# TapTempoMk2.net
KiCad netlist of a schematic drawn in EAGLE
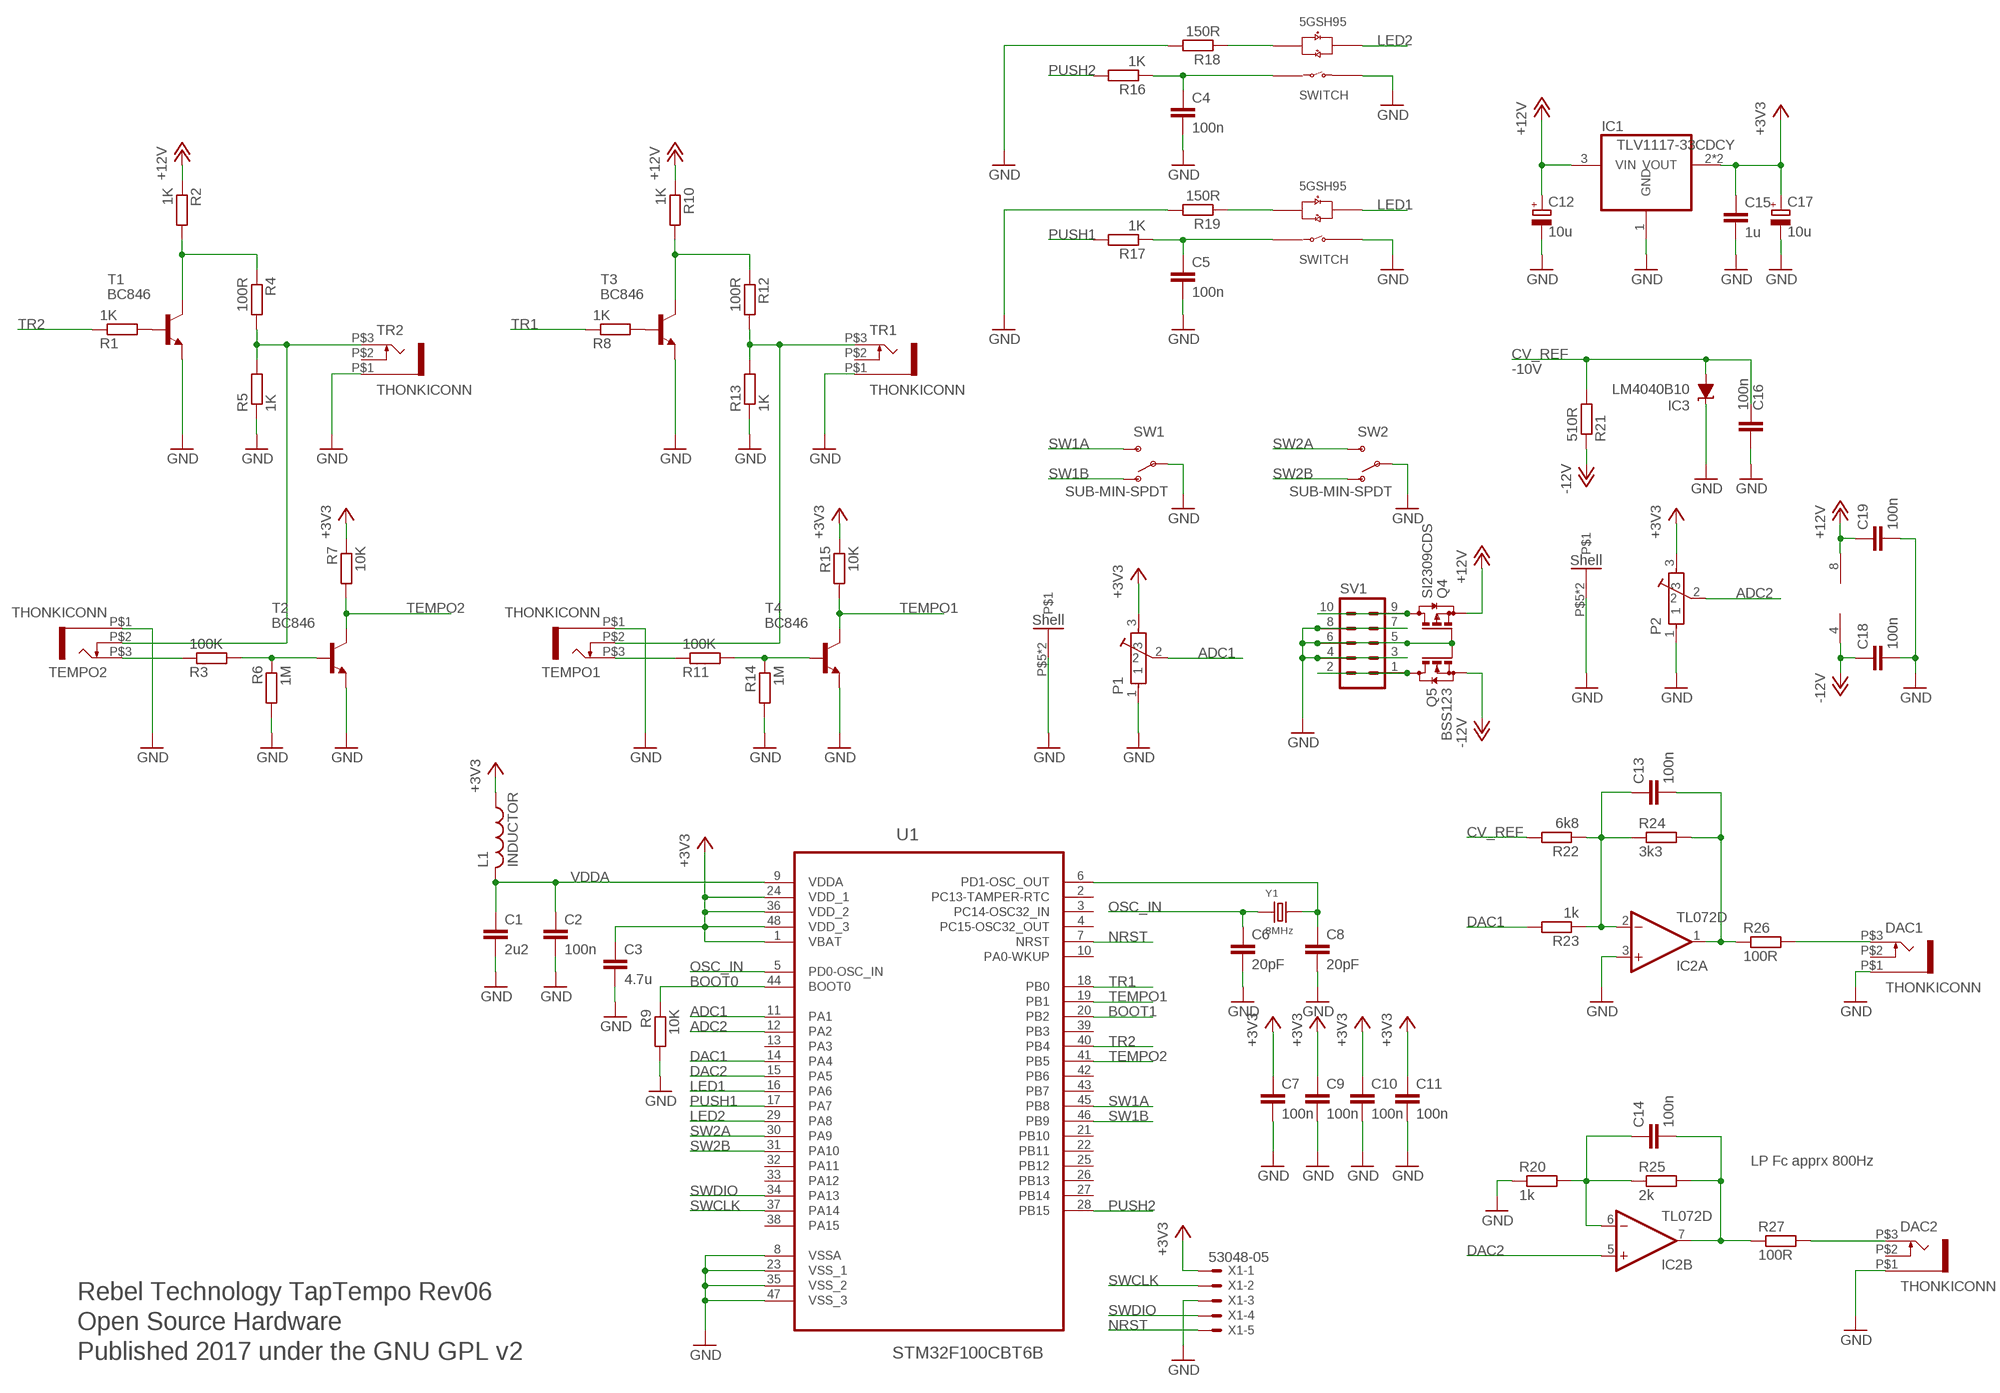
[diagram p0: schematic, sheet 1]

(export (version "E")
  (design (tool "Eeschema 10.0.6"))
  (components
    (comp (ref "C1")
      (value "2u2")
      (footprint "eagle-import:C0603")
      (libsource (lib "eagle-import") (part "C-EUC0603"))
    )
    (comp (ref "C2")
      (value "100n")
      (footprint "eagle-import:C0603")
      (libsource (lib "eagle-import") (part "C-EUC0603"))
    )
    (comp (ref "C3")
      (value "4.7u")
      (footprint "eagle-import:C0603")
      (libsource (lib "eagle-import") (part "C-EUC0603"))
    )
    (comp (ref "C4")
      (value "100n")
      (footprint "eagle-import:C0603")
      (libsource (lib "eagle-import") (part "C-EUC0603"))
    )
    (comp (ref "C5")
      (value "100n")
      (footprint "eagle-import:C0603")
      (libsource (lib "eagle-import") (part "C-EUC0603"))
    )
    (comp (ref "C6")
      (value "20pF")
      (footprint "eagle-import:C0603")
      (libsource (lib "eagle-import") (part "C-EUC0603"))
    )
    (comp (ref "C7")
      (value "100n")
      (footprint "eagle-import:C0603")
      (libsource (lib "eagle-import") (part "C-EUC0603"))
    )
    (comp (ref "C8")
      (value "20pF")
      (footprint "eagle-import:C0603")
      (libsource (lib "eagle-import") (part "C-EUC0603"))
    )
    (comp (ref "C9")
      (value "100n")
      (footprint "eagle-import:C0603")
      (libsource (lib "eagle-import") (part "C-EUC0603"))
    )
    (comp (ref "C10")
      (value "100n")
      (footprint "eagle-import:C0603")
      (libsource (lib "eagle-import") (part "C-EUC0603"))
    )
    (comp (ref "C11")
      (value "100n")
      (footprint "eagle-import:C0603")
      (libsource (lib "eagle-import") (part "C-EUC0603"))
    )
    (comp (ref "C12")
      (value "10u")
      (footprint "eagle-import:153CLV-0405")
      (libsource (lib "eagle-import") (part "CPOL-EU153CLV-0405"))
    )
    (comp (ref "C13")
      (value "100n")
      (footprint "eagle-import:C0603")
      (libsource (lib "eagle-import") (part "C-EUC0603"))
    )
    (comp (ref "C14")
      (value "100n")
      (footprint "eagle-import:C0603")
      (libsource (lib "eagle-import") (part "C-EUC0603"))
    )
    (comp (ref "C15")
      (value "1u")
      (footprint "eagle-import:C0603")
      (libsource (lib "eagle-import") (part "C-EUC0603"))
    )
    (comp (ref "C16")
      (value "100n")
      (footprint "eagle-import:C0603")
      (libsource (lib "eagle-import") (part "C-EUC0603"))
    )
    (comp (ref "C17")
      (value "10u")
      (footprint "eagle-import:153CLV-0405")
      (libsource (lib "eagle-import") (part "CPOL-EU153CLV-0405"))
    )
    (comp (ref "C18")
      (value "100n")
      (footprint "eagle-import:C0603")
      (libsource (lib "eagle-import") (part "C-EUC0603"))
    )
    (comp (ref "C19")
      (value "100n")
      (footprint "eagle-import:C0603")
      (libsource (lib "eagle-import") (part "C-EUC0603"))
    )
    (comp (ref "DAC1")
      (value "THONKICONN")
      (footprint "eagle-import:THONKICONN")
      (libsource (lib "eagle-import") (part "THONKICONN"))
    )
    (comp (ref "DAC2")
      (value "THONKICONN")
      (footprint "eagle-import:THONKICONN")
      (libsource (lib "eagle-import") (part "THONKICONN"))
    )
    (comp (ref "IC1")
      (value "TLV1117-33CDCY")
      (footprint "eagle-import:SOT223")
      (fields (field (name "MPN") "REG1117"))
      (libsource (lib "eagle-import") (part "REG1117"))
    )
    (comp (ref "IC2")
      (value "TL072D")
      (footprint "eagle-import:SO08")
      (libsource (lib "eagle-import") (part "TL072D"))
    )
    (comp (ref "IC3")
      (value "LM4040B10")
      (footprint "eagle-import:DBZ_R-PDSO-G3")
      (fields (field (name "MF") "TEXAS INSTRUMENT CONNECTORS") (field (name "MPN") "LM4041C12QDBZT"))
      (libsource (lib "eagle-import") (part "LM4041DBZC12"))
    )
    (comp (ref "L1")
      (value "INDUCTOR")
      (footprint "eagle-import:0603")
      (libsource (lib "eagle-import") (part "INDUCTOR"))
    )
    (comp (ref "P1")
      (value "POT-ALPS-RK09L1140")
      (footprint "eagle-import:POT-ALPS-RK09L1140")
      (libsource (lib "eagle-import") (part "POT-ALPS-RK09L1140"))
    )
    (comp (ref "P2")
      (value "POT-ALPS-RK09L1140")
      (footprint "eagle-import:POT-ALPS-RK09L1140")
      (libsource (lib "eagle-import") (part "POT-ALPS-RK09L1140"))
    )
    (comp (ref "PUSH1")
      (value "5GTH9")
      (footprint "eagle-import:5GTH9")
      (libsource (lib "eagle-import") (part "5GTH9"))
    )
    (comp (ref "PUSH2")
      (value "5GTH9")
      (footprint "eagle-import:5GTH9")
      (libsource (lib "eagle-import") (part "5GTH9"))
    )
    (comp (ref "Q4")
      (value "SI2309CDS")
      (footprint "eagle-import:SOT23")
      (libsource (lib "eagle-import") (part "BSS84"))
    )
    (comp (ref "Q5")
      (value "BSS123")
      (footprint "eagle-import:SOT23")
      (libsource (lib "eagle-import") (part "BSS123"))
    )
    (comp (ref "R1")
      (value "1K")
      (footprint "eagle-import:0603")
      (libsource (lib "eagle-import") (part "R-EU_0603"))
    )
    (comp (ref "R2")
      (value "1K")
      (footprint "eagle-import:0603")
      (libsource (lib "eagle-import") (part "R-EU_0603"))
    )
    (comp (ref "R3")
      (value "100K")
      (footprint "eagle-import:0603")
      (libsource (lib "eagle-import") (part "R-EU_0603"))
    )
    (comp (ref "R4")
      (value "100R")
      (footprint "eagle-import:0603")
      (libsource (lib "eagle-import") (part "R-EU_0603"))
    )
    (comp (ref "R5")
      (value "1K")
      (footprint "eagle-import:0603")
      (libsource (lib "eagle-import") (part "R-EU_0603"))
    )
    (comp (ref "R6")
      (value "1M")
      (footprint "eagle-import:0603")
      (libsource (lib "eagle-import") (part "R-EU_0603"))
    )
    (comp (ref "R7")
      (value "10K")
      (footprint "eagle-import:0603")
      (libsource (lib "eagle-import") (part "R-EU_0603"))
    )
    (comp (ref "R8")
      (value "1K")
      (footprint "eagle-import:0603")
      (libsource (lib "eagle-import") (part "R-EU_0603"))
    )
    (comp (ref "R9")
      (value "10K")
      (footprint "eagle-import:0603")
      (libsource (lib "eagle-import") (part "R-EU_0603"))
    )
    (comp (ref "R10")
      (value "1K")
      (footprint "eagle-import:0603")
      (libsource (lib "eagle-import") (part "R-EU_0603"))
    )
    (comp (ref "R11")
      (value "100K")
      (footprint "eagle-import:0603")
      (libsource (lib "eagle-import") (part "R-EU_0603"))
    )
    (comp (ref "R12")
      (value "100R")
      (footprint "eagle-import:0603")
      (libsource (lib "eagle-import") (part "R-EU_0603"))
    )
    (comp (ref "R13")
      (value "1K")
      (footprint "eagle-import:0603")
      (libsource (lib "eagle-import") (part "R-EU_0603"))
    )
    (comp (ref "R14")
      (value "1M")
      (footprint "eagle-import:0603")
      (libsource (lib "eagle-import") (part "R-EU_0603"))
    )
    (comp (ref "R15")
      (value "10K")
      (footprint "eagle-import:0603")
      (libsource (lib "eagle-import") (part "R-EU_0603"))
    )
    (comp (ref "R16")
      (value "1K")
      (footprint "eagle-import:0603")
      (libsource (lib "eagle-import") (part "R-EU_0603"))
    )
    (comp (ref "R17")
      (value "1K")
      (footprint "eagle-import:0603")
      (libsource (lib "eagle-import") (part "R-EU_0603"))
    )
    (comp (ref "R18")
      (value "150R")
      (footprint "eagle-import:0603")
      (libsource (lib "eagle-import") (part "R-EU_0603"))
    )
    (comp (ref "R19")
      (value "150R")
      (footprint "eagle-import:0603")
      (libsource (lib "eagle-import") (part "R-EU_0603"))
    )
    (comp (ref "R20")
      (value "1k")
      (footprint "eagle-import:0603")
      (libsource (lib "eagle-import") (part "R-EU_0603"))
    )
    (comp (ref "R21")
      (value "510R")
      (footprint "eagle-import:0603")
      (libsource (lib "eagle-import") (part "R-EU_0603"))
    )
    (comp (ref "R22")
      (value "6k8")
      (footprint "eagle-import:0603")
      (libsource (lib "eagle-import") (part "R-EU_0603"))
    )
    (comp (ref "R23")
      (value "1k")
      (footprint "eagle-import:0603")
      (libsource (lib "eagle-import") (part "R-EU_0603"))
    )
    (comp (ref "R24")
      (value "3k3")
      (footprint "eagle-import:0603")
      (libsource (lib "eagle-import") (part "R-EU_0603"))
    )
    (comp (ref "R25")
      (value "2k")
      (footprint "eagle-import:0603")
      (libsource (lib "eagle-import") (part "R-EU_0603"))
    )
    (comp (ref "R26")
      (value "100R")
      (footprint "eagle-import:0603")
      (libsource (lib "eagle-import") (part "R-EU_0603"))
    )
    (comp (ref "R27")
      (value "100R")
      (footprint "eagle-import:0603")
      (libsource (lib "eagle-import") (part "R-EU_0603"))
    )
    (comp (ref "SV1")
      (value "MA05-2")
      (footprint "eagle-import:MA05-2")
      (libsource (lib "eagle-import") (part "MA05-2"))
    )
    (comp (ref "SW1")
      (value "SUB-MIN-SPDT")
      (footprint "eagle-import:SUB-MIN-SPDT")
      (libsource (lib "eagle-import") (part "SUB-MIN-SPDT"))
    )
    (comp (ref "SW2")
      (value "SUB-MIN-SPDT")
      (footprint "eagle-import:SUB-MIN-SPDT")
      (libsource (lib "eagle-import") (part "SUB-MIN-SPDT"))
    )
    (comp (ref "T1")
      (value "BC846")
      (footprint "eagle-import:SOT23")
      (libsource (lib "eagle-import") (part "BC846"))
    )
    (comp (ref "T2")
      (value "BC846")
      (footprint "eagle-import:SOT23")
      (libsource (lib "eagle-import") (part "BC846"))
    )
    (comp (ref "T3")
      (value "BC846")
      (footprint "eagle-import:SOT23")
      (libsource (lib "eagle-import") (part "BC846"))
    )
    (comp (ref "T4")
      (value "BC846")
      (footprint "eagle-import:SOT23")
      (libsource (lib "eagle-import") (part "BC846"))
    )
    (comp (ref "TEMPO1")
      (value "THONKICONN")
      (footprint "eagle-import:THONKICONN")
      (libsource (lib "eagle-import") (part "THONKICONN"))
    )
    (comp (ref "TEMPO2")
      (value "THONKICONN")
      (footprint "eagle-import:THONKICONN")
      (libsource (lib "eagle-import") (part "THONKICONN"))
    )
    (comp (ref "TR1")
      (value "THONKICONN")
      (footprint "eagle-import:THONKICONN")
      (libsource (lib "eagle-import") (part "THONKICONN"))
    )
    (comp (ref "TR2")
      (value "THONKICONN")
      (footprint "eagle-import:THONKICONN")
      (libsource (lib "eagle-import") (part "THONKICONN"))
    )
    (comp (ref "U1")
      (value "STM32F100CBT6B")
      (footprint "eagle-import:QFP50P900X900X160-48N")
      (libsource (lib "eagle-import") (part "STM32F100CBT6B"))
    )
    (comp (ref "X1")
      (value "53048-05")
      (footprint "eagle-import:53048-05")
      (fields (field (name "MF") "MOLEX") (field (name "MPN") "53048-0510"))
      (libsource (lib "eagle-import") (part "53?-05048"))
    )
    (comp (ref "Y1")
      (value "8MHz")
      (footprint "eagle-import:X2-SMD-5.0X3.2X1.3MM")
      (fields (field (name "MPN") "5032/2P"))
      (libsource (lib "eagle-import") (part "SMD-CRYSTAL-8MHZ-20PF-20PPM(2P-5.0X3.2MM)"))
    )
  )
  (nets
    (net (code "1") (name "+3V3") (class "Default")
      (node (ref "C10") (pin "1") (pinfunction "1_1") (pintype "passive"))
      (node (ref "C11") (pin "1") (pinfunction "1_1") (pintype "passive"))
      (node (ref "C15") (pin "1") (pinfunction "1_1") (pintype "passive"))
      (node (ref "C17") (pin "+") (pinfunction "+_+") (pintype "passive"))
      (node (ref "C3") (pin "1") (pinfunction "1_1") (pintype "passive"))
      (node (ref "C7") (pin "1") (pinfunction "1_1") (pintype "passive"))
      (node (ref "C9") (pin "1") (pinfunction "1_1") (pintype "passive"))
      (node (ref "IC1") (pin "2") (pinfunction "VOUT_2") (pintype "output"))
      (node (ref "IC1") (pin "4") (pinfunction "VOUT_4") (pintype "output"))
      (node (ref "L1") (pin "1") (pinfunction "1_1") (pintype "passive"))
      (node (ref "P1") (pin "3") (pinfunction "3_3") (pintype "bidirectional"))
      (node (ref "P2") (pin "3") (pinfunction "3_3") (pintype "bidirectional"))
      (node (ref "R15") (pin "1") (pinfunction "1_1") (pintype "passive"))
      (node (ref "R7") (pin "1") (pinfunction "1_1") (pintype "passive"))
      (node (ref "U1") (pin "1") (pinfunction "VBAT_1") (pintype "power_in"))
      (node (ref "U1") (pin "24") (pinfunction "VDD_1_24") (pintype "power_in"))
      (node (ref "U1") (pin "36") (pinfunction "VDD_2_36") (pintype "power_in"))
      (node (ref "U1") (pin "48") (pinfunction "VDD_3_48") (pintype "power_in"))
      (node (ref "X1") (pin "1") (pinfunction "S_1") (pintype "passive"))
    )
    (net (code "2") (name "+12V") (class "Default")
      (node (ref "C12") (pin "+") (pinfunction "+_+") (pintype "passive"))
      (node (ref "C19") (pin "1") (pinfunction "1_1") (pintype "passive"))
      (node (ref "IC1") (pin "3") (pinfunction "VIN_3") (pintype "input"))
      (node (ref "IC2") (pin "8") (pinfunction "V+_8") (pintype "power_in"))
      (node (ref "Q4") (pin "2") (pinfunction "S_2") (pintype "passive"))
      (node (ref "R10") (pin "1") (pinfunction "1_1") (pintype "passive"))
      (node (ref "R2") (pin "1") (pinfunction "1_1") (pintype "passive"))
    )
    (net (code "3") (name "-12V") (class "Default")
      (node (ref "C18") (pin "1") (pinfunction "1_1") (pintype "passive"))
      (node (ref "IC2") (pin "4") (pinfunction "V-_4") (pintype "power_in"))
      (node (ref "Q5") (pin "2") (pinfunction "S_2") (pintype "passive"))
      (node (ref "R21") (pin "1") (pinfunction "1_1") (pintype "passive"))
    )
    (net (code "4") (name "/ADC1") (class "Default")
      (node (ref "P1") (pin "2") (pinfunction "2_2") (pintype "bidirectional"))
      (node (ref "U1") (pin "11") (pinfunction "PA1_11") (pintype "bidirectional"))
    )
    (net (code "5") (name "/ADC2") (class "Default")
      (node (ref "P2") (pin "2") (pinfunction "2_2") (pintype "bidirectional"))
      (node (ref "U1") (pin "12") (pinfunction "PA2_12") (pintype "bidirectional"))
    )
    (net (code "6") (name "/BOOT0") (class "Default")
      (node (ref "R9") (pin "1") (pinfunction "1_1") (pintype "passive"))
      (node (ref "U1") (pin "44") (pinfunction "BOOT0_44") (pintype "input"))
    )
    (net (code "7") (name "/BOOT1") (class "Default")
      (node (ref "U1") (pin "20") (pinfunction "PB2_20") (pintype "bidirectional"))
    )
    (net (code "8") (name "/CV_REF") (class "Default")
      (node (ref "C16") (pin "1") (pinfunction "1_1") (pintype "passive"))
      (node (ref "IC3") (pin "2") (pinfunction "A_2") (pintype "passive"))
      (node (ref "R21") (pin "2") (pinfunction "2_2") (pintype "passive"))
      (node (ref "R22") (pin "2") (pinfunction "2_2") (pintype "passive"))
    )
    (net (code "9") (name "/DAC1") (class "Default")
      (node (ref "R23") (pin "2") (pinfunction "2_2") (pintype "passive"))
      (node (ref "U1") (pin "14") (pinfunction "PA4_14") (pintype "bidirectional"))
    )
    (net (code "10") (name "/DAC2") (class "Default")
      (node (ref "IC2") (pin "5") (pinfunction "+IN_5") (pintype "input"))
      (node (ref "U1") (pin "15") (pinfunction "PA5_15") (pintype "bidirectional"))
    )
    (net (code "11") (name "/LED1") (class "Default")
      (node (ref "PUSH1") (pin "+3") (pinfunction "LED_R+_+3") (pintype "bidirectional"))
      (node (ref "U1") (pin "16") (pinfunction "PA6_16") (pintype "bidirectional"))
    )
    (net (code "12") (name "/LED2") (class "Default")
      (node (ref "PUSH2") (pin "+3") (pinfunction "LED_R+_+3") (pintype "bidirectional"))
      (node (ref "U1") (pin "29") (pinfunction "PA8_29") (pintype "bidirectional"))
    )
    (net (code "13") (name "/NRST") (class "Default")
      (node (ref "U1") (pin "7") (pinfunction "NRST_7") (pintype "bidirectional"))
      (node (ref "X1") (pin "5") (pinfunction "S_5") (pintype "passive"))
    )
    (net (code "14") (name "/OSC_IN") (class "Default")
      (node (ref "C6") (pin "1") (pinfunction "1_1") (pintype "passive"))
      (node (ref "U1") (pin "5") (pinfunction "PD0-OSC_IN_5") (pintype "input"))
      (node (ref "Y1") (pin "1") (pinfunction "1_1") (pintype "passive"))
    )
    (net (code "15") (name "/PUSH1") (class "Default")
      (node (ref "R17") (pin "2") (pinfunction "2_2") (pintype "passive"))
      (node (ref "U1") (pin "17") (pinfunction "PA7_17") (pintype "bidirectional"))
    )
    (net (code "16") (name "/PUSH2") (class "Default")
      (node (ref "R16") (pin "2") (pinfunction "2_2") (pintype "passive"))
      (node (ref "U1") (pin "28") (pinfunction "PB15_28") (pintype "bidirectional"))
    )
    (net (code "17") (name "/SW1A") (class "Default")
      (node (ref "SW1") (pin "3") (pinfunction "S_3") (pintype "passive"))
      (node (ref "U1") (pin "45") (pinfunction "PB8_45") (pintype "bidirectional"))
    )
    (net (code "18") (name "/SW1B") (class "Default")
      (node (ref "SW1") (pin "1") (pinfunction "O_1") (pintype "passive"))
      (node (ref "U1") (pin "46") (pinfunction "PB9_46") (pintype "bidirectional"))
    )
    (net (code "19") (name "/SW2A") (class "Default")
      (node (ref "SW2") (pin "3") (pinfunction "S_3") (pintype "passive"))
      (node (ref "U1") (pin "30") (pinfunction "PA9_30") (pintype "bidirectional"))
    )
    (net (code "20") (name "/SW2B") (class "Default")
      (node (ref "SW2") (pin "1") (pinfunction "O_1") (pintype "passive"))
      (node (ref "U1") (pin "31") (pinfunction "PA10_31") (pintype "bidirectional"))
    )
    (net (code "21") (name "/SWCLK") (class "Default")
      (node (ref "U1") (pin "37") (pinfunction "PA14_37") (pintype "bidirectional"))
      (node (ref "X1") (pin "2") (pinfunction "S_2") (pintype "passive"))
    )
    (net (code "22") (name "/SWDIO") (class "Default")
      (node (ref "U1") (pin "34") (pinfunction "PA13_34") (pintype "bidirectional"))
      (node (ref "X1") (pin "4") (pinfunction "S_4") (pintype "passive"))
    )
    (net (code "23") (name "/TEMPO1") (class "Default")
      (node (ref "R15") (pin "2") (pinfunction "2_2") (pintype "passive"))
      (node (ref "T4") (pin "3") (pinfunction "C_3") (pintype "passive"))
      (node (ref "U1") (pin "19") (pinfunction "PB1_19") (pintype "bidirectional"))
    )
    (net (code "24") (name "/TEMPO2") (class "Default")
      (node (ref "R7") (pin "2") (pinfunction "2_2") (pintype "passive"))
      (node (ref "T2") (pin "3") (pinfunction "C_3") (pintype "passive"))
      (node (ref "U1") (pin "41") (pinfunction "PB5_41") (pintype "bidirectional"))
    )
    (net (code "25") (name "/TR1") (class "Default")
      (node (ref "R8") (pin "1") (pinfunction "1_1") (pintype "passive"))
      (node (ref "U1") (pin "18") (pinfunction "PB0_18") (pintype "bidirectional"))
    )
    (net (code "26") (name "/TR2") (class "Default")
      (node (ref "R1") (pin "1") (pinfunction "1_1") (pintype "passive"))
      (node (ref "U1") (pin "40") (pinfunction "PB4_40") (pintype "bidirectional"))
    )
    (net (code "27") (name "/VDDA") (class "Default")
      (node (ref "C1") (pin "1") (pinfunction "1_1") (pintype "passive"))
      (node (ref "C2") (pin "1") (pinfunction "1_1") (pintype "passive"))
      (node (ref "L1") (pin "2") (pinfunction "2_2") (pintype "passive"))
      (node (ref "U1") (pin "9") (pinfunction "VDDA_9") (pintype "power_in"))
    )
    (net (code "28") (name "GND") (class "Default")
      (node (ref "C1") (pin "2") (pinfunction "2_2") (pintype "passive"))
      (node (ref "C10") (pin "2") (pinfunction "2_2") (pintype "passive"))
      (node (ref "C11") (pin "2") (pinfunction "2_2") (pintype "passive"))
      (node (ref "C12") (pin "-") (pinfunction "-_-") (pintype "passive"))
      (node (ref "C15") (pin "2") (pinfunction "2_2") (pintype "passive"))
      (node (ref "C16") (pin "2") (pinfunction "2_2") (pintype "passive"))
      (node (ref "C17") (pin "-") (pinfunction "-_-") (pintype "passive"))
      (node (ref "C18") (pin "2") (pinfunction "2_2") (pintype "passive"))
      (node (ref "C19") (pin "2") (pinfunction "2_2") (pintype "passive"))
      (node (ref "C2") (pin "2") (pinfunction "2_2") (pintype "passive"))
      (node (ref "C3") (pin "2") (pinfunction "2_2") (pintype "passive"))
      (node (ref "C4") (pin "2") (pinfunction "2_2") (pintype "passive"))
      (node (ref "C5") (pin "2") (pinfunction "2_2") (pintype "passive"))
      (node (ref "C6") (pin "2") (pinfunction "2_2") (pintype "passive"))
      (node (ref "C7") (pin "2") (pinfunction "2_2") (pintype "passive"))
      (node (ref "C8") (pin "2") (pinfunction "2_2") (pintype "passive"))
      (node (ref "C9") (pin "2") (pinfunction "2_2") (pintype "passive"))
      (node (ref "DAC1") (pin "P$1") (pinfunction "5_P$1") (pintype "passive"))
      (node (ref "DAC2") (pin "P$1") (pinfunction "5_P$1") (pintype "passive"))
      (node (ref "IC1") (pin "1") (pinfunction "GND_1") (pintype "power_in"))
      (node (ref "IC2") (pin "3") (pinfunction "+IN_3") (pintype "input"))
      (node (ref "IC3") (pin "1") (pinfunction "C_1") (pintype "passive"))
      (node (ref "P1") (pin "1") (pinfunction "1_1") (pintype "bidirectional"))
      (node (ref "P1") (pin "P$5") (pinfunction "P$1_P$5") (pintype "bidirectional"))
      (node (ref "P1") (pin "P$6") (pinfunction "P$1_P$6") (pintype "bidirectional"))
      (node (ref "P2") (pin "1") (pinfunction "1_1") (pintype "bidirectional"))
      (node (ref "P2") (pin "P$5") (pinfunction "P$1_P$5") (pintype "bidirectional"))
      (node (ref "P2") (pin "P$6") (pinfunction "P$1_P$6") (pintype "bidirectional"))
      (node (ref "PUSH1") (pin "1") (pinfunction "SWITCH_B_1") (pintype "bidirectional"))
      (node (ref "PUSH2") (pin "1") (pinfunction "SWITCH_B_1") (pintype "bidirectional"))
      (node (ref "Q4") (pin "1") (pinfunction "G_1") (pintype "passive"))
      (node (ref "Q5") (pin "1") (pinfunction "G_1") (pintype "passive"))
      (node (ref "R13") (pin "1") (pinfunction "1_1") (pintype "passive"))
      (node (ref "R14") (pin "2") (pinfunction "2_2") (pintype "passive"))
      (node (ref "R18") (pin "2") (pinfunction "2_2") (pintype "passive"))
      (node (ref "R19") (pin "2") (pinfunction "2_2") (pintype "passive"))
      (node (ref "R20") (pin "1") (pinfunction "1_1") (pintype "passive"))
      (node (ref "R5") (pin "1") (pinfunction "1_1") (pintype "passive"))
      (node (ref "R6") (pin "2") (pinfunction "2_2") (pintype "passive"))
      (node (ref "R9") (pin "2") (pinfunction "2_2") (pintype "passive"))
      (node (ref "SV1") (pin "3") (pinfunction "3_3") (pintype "passive"))
      (node (ref "SV1") (pin "4") (pinfunction "4_4") (pintype "passive"))
      (node (ref "SV1") (pin "5") (pinfunction "5_5") (pintype "passive"))
      (node (ref "SV1") (pin "6") (pinfunction "6_6") (pintype "passive"))
      (node (ref "SV1") (pin "7") (pinfunction "7_7") (pintype "passive"))
      (node (ref "SV1") (pin "8") (pinfunction "8_8") (pintype "passive"))
      (node (ref "SW1") (pin "2") (pinfunction "P_2") (pintype "passive"))
      (node (ref "SW2") (pin "2") (pinfunction "P_2") (pintype "passive"))
      (node (ref "T1") (pin "2") (pinfunction "E_2") (pintype "passive"))
      (node (ref "T2") (pin "2") (pinfunction "E_2") (pintype "passive"))
      (node (ref "T3") (pin "2") (pinfunction "E_2") (pintype "passive"))
      (node (ref "T4") (pin "2") (pinfunction "E_2") (pintype "passive"))
      (node (ref "TEMPO1") (pin "P$1") (pinfunction "5_P$1") (pintype "passive"))
      (node (ref "TEMPO2") (pin "P$1") (pinfunction "5_P$1") (pintype "passive"))
      (node (ref "TR1") (pin "P$1") (pinfunction "5_P$1") (pintype "passive"))
      (node (ref "TR2") (pin "P$1") (pinfunction "5_P$1") (pintype "passive"))
      (node (ref "U1") (pin "23") (pinfunction "VSS_1_23") (pintype "power_in"))
      (node (ref "U1") (pin "35") (pinfunction "VSS_2_35") (pintype "power_in"))
      (node (ref "U1") (pin "47") (pinfunction "VSS_3_47") (pintype "power_in"))
      (node (ref "U1") (pin "8") (pinfunction "VSSA_8") (pintype "power_in"))
      (node (ref "X1") (pin "3") (pinfunction "S_3") (pintype "passive"))
    )
    (net (code "29") (name "Net-(DAC1-3)") (class "Default")
      (node (ref "DAC1") (pin "P$3") (pinfunction "3_P$3") (pintype "passive"))
      (node (ref "R26") (pin "2") (pinfunction "2_2") (pintype "passive"))
    )
    (net (code "30") (name "Net-(DAC2-3)") (class "Default")
      (node (ref "DAC2") (pin "P$3") (pinfunction "3_P$3") (pintype "passive"))
      (node (ref "R27") (pin "2") (pinfunction "2_2") (pintype "passive"))
    )
    (net (code "31") (name "Net-(IC2A--IN)") (class "Default")
      (node (ref "C13") (pin "1") (pinfunction "1_1") (pintype "passive"))
      (node (ref "IC2") (pin "2") (pinfunction "-IN_2") (pintype "input"))
      (node (ref "R22") (pin "1") (pinfunction "1_1") (pintype "passive"))
      (node (ref "R23") (pin "1") (pinfunction "1_1") (pintype "passive"))
      (node (ref "R24") (pin "1") (pinfunction "1_1") (pintype "passive"))
    )
    (net (code "32") (name "Net-(IC2A-OUT)") (class "Default")
      (node (ref "C13") (pin "2") (pinfunction "2_2") (pintype "passive"))
      (node (ref "IC2") (pin "1") (pinfunction "OUT_1") (pintype "output"))
      (node (ref "R24") (pin "2") (pinfunction "2_2") (pintype "passive"))
      (node (ref "R26") (pin "1") (pinfunction "1_1") (pintype "passive"))
    )
    (net (code "33") (name "Net-(IC2B--IN)") (class "Default")
      (node (ref "C14") (pin "1") (pinfunction "1_1") (pintype "passive"))
      (node (ref "IC2") (pin "6") (pinfunction "-IN_6") (pintype "input"))
      (node (ref "R20") (pin "2") (pinfunction "2_2") (pintype "passive"))
      (node (ref "R25") (pin "1") (pinfunction "1_1") (pintype "passive"))
    )
    (net (code "34") (name "Net-(IC2B-OUT)") (class "Default")
      (node (ref "C14") (pin "2") (pinfunction "2_2") (pintype "passive"))
      (node (ref "IC2") (pin "7") (pinfunction "OUT_7") (pintype "output"))
      (node (ref "R25") (pin "2") (pinfunction "2_2") (pintype "passive"))
      (node (ref "R27") (pin "1") (pinfunction "1_1") (pintype "passive"))
    )
    (net (code "35") (name "Net-(PUSH1-LED_G+)") (class "Default")
      (node (ref "PUSH1") (pin "-2") (pinfunction "LED_G+_-2") (pintype "bidirectional"))
      (node (ref "R19") (pin "1") (pinfunction "1_1") (pintype "passive"))
    )
    (net (code "36") (name "Net-(PUSH1-SWITCH_A)") (class "Default")
      (node (ref "C5") (pin "1") (pinfunction "1_1") (pintype "passive"))
      (node (ref "PUSH1") (pin "4") (pinfunction "SWITCH_A_4") (pintype "bidirectional"))
      (node (ref "R17") (pin "1") (pinfunction "1_1") (pintype "passive"))
    )
    (net (code "37") (name "Net-(PUSH2-LED_G+)") (class "Default")
      (node (ref "PUSH2") (pin "-2") (pinfunction "LED_G+_-2") (pintype "bidirectional"))
      (node (ref "R18") (pin "1") (pinfunction "1_1") (pintype "passive"))
    )
    (net (code "38") (name "Net-(PUSH2-SWITCH_A)") (class "Default")
      (node (ref "C4") (pin "1") (pinfunction "1_1") (pintype "passive"))
      (node (ref "PUSH2") (pin "4") (pinfunction "SWITCH_A_4") (pintype "bidirectional"))
      (node (ref "R16") (pin "1") (pinfunction "1_1") (pintype "passive"))
    )
    (net (code "39") (name "Net-(Q4-D)") (class "Default")
      (node (ref "Q4") (pin "3") (pinfunction "D_3") (pintype "passive"))
      (node (ref "SV1") (pin "10") (pinfunction "10_10") (pintype "passive"))
      (node (ref "SV1") (pin "9") (pinfunction "9_9") (pintype "passive"))
    )
    (net (code "40") (name "Net-(Q5-D)") (class "Default")
      (node (ref "Q5") (pin "3") (pinfunction "D_3") (pintype "passive"))
      (node (ref "SV1") (pin "1") (pinfunction "1_1") (pintype "passive"))
      (node (ref "SV1") (pin "2") (pinfunction "2_2") (pintype "passive"))
    )
    (net (code "41") (name "Net-(T1-B)") (class "Default")
      (node (ref "R1") (pin "2") (pinfunction "2_2") (pintype "passive"))
      (node (ref "T1") (pin "1") (pinfunction "B_1") (pintype "passive"))
    )
    (net (code "42") (name "Net-(T1-C)") (class "Default")
      (node (ref "R2") (pin "2") (pinfunction "2_2") (pintype "passive"))
      (node (ref "R4") (pin "1") (pinfunction "1_1") (pintype "passive"))
      (node (ref "T1") (pin "3") (pinfunction "C_3") (pintype "passive"))
    )
    (net (code "43") (name "Net-(T2-B)") (class "Default")
      (node (ref "R3") (pin "2") (pinfunction "2_2") (pintype "passive"))
      (node (ref "R6") (pin "1") (pinfunction "1_1") (pintype "passive"))
      (node (ref "T2") (pin "1") (pinfunction "B_1") (pintype "passive"))
    )
    (net (code "44") (name "Net-(T3-B)") (class "Default")
      (node (ref "R8") (pin "2") (pinfunction "2_2") (pintype "passive"))
      (node (ref "T3") (pin "1") (pinfunction "B_1") (pintype "passive"))
    )
    (net (code "45") (name "Net-(T3-C)") (class "Default")
      (node (ref "R10") (pin "2") (pinfunction "2_2") (pintype "passive"))
      (node (ref "R12") (pin "1") (pinfunction "1_1") (pintype "passive"))
      (node (ref "T3") (pin "3") (pinfunction "C_3") (pintype "passive"))
    )
    (net (code "46") (name "Net-(T4-B)") (class "Default")
      (node (ref "R11") (pin "2") (pinfunction "2_2") (pintype "passive"))
      (node (ref "R14") (pin "1") (pinfunction "1_1") (pintype "passive"))
      (node (ref "T4") (pin "1") (pinfunction "B_1") (pintype "passive"))
    )
    (net (code "47") (name "Net-(TEMPO1-3)") (class "Default")
      (node (ref "R11") (pin "1") (pinfunction "1_1") (pintype "passive"))
      (node (ref "TEMPO1") (pin "P$3") (pinfunction "3_P$3") (pintype "passive"))
    )
    (net (code "48") (name "Net-(TEMPO1-4)") (class "Default")
      (node (ref "R12") (pin "2") (pinfunction "2_2") (pintype "passive"))
      (node (ref "R13") (pin "2") (pinfunction "2_2") (pintype "passive"))
      (node (ref "TEMPO1") (pin "P$2") (pinfunction "4_P$2") (pintype "passive"))
      (node (ref "TR1") (pin "P$3") (pinfunction "3_P$3") (pintype "passive"))
    )
    (net (code "49") (name "Net-(TEMPO2-3)") (class "Default")
      (node (ref "R3") (pin "1") (pinfunction "1_1") (pintype "passive"))
      (node (ref "TEMPO2") (pin "P$3") (pinfunction "3_P$3") (pintype "passive"))
    )
    (net (code "50") (name "Net-(TEMPO2-4)") (class "Default")
      (node (ref "R4") (pin "2") (pinfunction "2_2") (pintype "passive"))
      (node (ref "R5") (pin "2") (pinfunction "2_2") (pintype "passive"))
      (node (ref "TEMPO2") (pin "P$2") (pinfunction "4_P$2") (pintype "passive"))
      (node (ref "TR2") (pin "P$3") (pinfunction "3_P$3") (pintype "passive"))
    )
    (net (code "51") (name "Net-(U1-PD1-OSC_OUT)") (class "Default")
      (node (ref "C8") (pin "1") (pinfunction "1_1") (pintype "passive"))
      (node (ref "U1") (pin "6") (pinfunction "PD1-OSC_OUT_6") (pintype "output"))
      (node (ref "Y1") (pin "2") (pinfunction "2_2") (pintype "passive"))
    )
    (net (code "52") (name "unconnected-(DAC1-4-PadP$2)") (class "Default")
      (node (ref "DAC1") (pin "P$2") (pinfunction "4_P$2") (pintype "passive"))
    )
    (net (code "53") (name "unconnected-(DAC2-4-PadP$2)") (class "Default")
      (node (ref "DAC2") (pin "P$2") (pinfunction "4_P$2") (pintype "passive"))
    )
    (net (code "54") (name "unconnected-(TR1-4-PadP$2)") (class "Default")
      (node (ref "TR1") (pin "P$2") (pinfunction "4_P$2") (pintype "passive"))
    )
    (net (code "55") (name "unconnected-(TR2-4-PadP$2)") (class "Default")
      (node (ref "TR2") (pin "P$2") (pinfunction "4_P$2") (pintype "passive"))
    )
    (net (code "56") (name "unconnected-(U1-PA0-WKUP-Pad10)") (class "Default")
      (node (ref "U1") (pin "10") (pinfunction "PA0-WKUP_10") (pintype "bidirectional"))
    )
    (net (code "57") (name "unconnected-(U1-PA3-Pad13)") (class "Default")
      (node (ref "U1") (pin "13") (pinfunction "PA3_13") (pintype "bidirectional"))
    )
    (net (code "58") (name "unconnected-(U1-PA11-Pad32)") (class "Default")
      (node (ref "U1") (pin "32") (pinfunction "PA11_32") (pintype "bidirectional"))
    )
    (net (code "59") (name "unconnected-(U1-PA12-Pad33)") (class "Default")
      (node (ref "U1") (pin "33") (pinfunction "PA12_33") (pintype "bidirectional"))
    )
    (net (code "60") (name "unconnected-(U1-PA15-Pad38)") (class "Default")
      (node (ref "U1") (pin "38") (pinfunction "PA15_38") (pintype "bidirectional"))
    )
    (net (code "61") (name "unconnected-(U1-PB3-Pad39)") (class "Default")
      (node (ref "U1") (pin "39") (pinfunction "PB3_39") (pintype "bidirectional"))
    )
    (net (code "62") (name "unconnected-(U1-PB6-Pad42)") (class "Default")
      (node (ref "U1") (pin "42") (pinfunction "PB6_42") (pintype "bidirectional"))
    )
    (net (code "63") (name "unconnected-(U1-PB7-Pad43)") (class "Default")
      (node (ref "U1") (pin "43") (pinfunction "PB7_43") (pintype "bidirectional"))
    )
    (net (code "64") (name "unconnected-(U1-PB10-Pad21)") (class "Default")
      (node (ref "U1") (pin "21") (pinfunction "PB10_21") (pintype "bidirectional"))
    )
    (net (code "65") (name "unconnected-(U1-PB11-Pad22)") (class "Default")
      (node (ref "U1") (pin "22") (pinfunction "PB11_22") (pintype "bidirectional"))
    )
    (net (code "66") (name "unconnected-(U1-PB12-Pad25)") (class "Default")
      (node (ref "U1") (pin "25") (pinfunction "PB12_25") (pintype "bidirectional"))
    )
    (net (code "67") (name "unconnected-(U1-PB13-Pad26)") (class "Default")
      (node (ref "U1") (pin "26") (pinfunction "PB13_26") (pintype "bidirectional"))
    )
    (net (code "68") (name "unconnected-(U1-PB14-Pad27)") (class "Default")
      (node (ref "U1") (pin "27") (pinfunction "PB14_27") (pintype "bidirectional"))
    )
    (net (code "69") (name "unconnected-(U1-PC13-TAMPER-RTC-Pad2)") (class "Default")
      (node (ref "U1") (pin "2") (pinfunction "PC13-TAMPER-RTC_2") (pintype "bidirectional"))
    )
    (net (code "70") (name "unconnected-(U1-PC14-OSC32_IN-Pad3)") (class "Default")
      (node (ref "U1") (pin "3") (pinfunction "PC14-OSC32_IN_3") (pintype "bidirectional"))
    )
    (net (code "71") (name "unconnected-(U1-PC15-OSC32_OUT-Pad4)") (class "Default")
      (node (ref "U1") (pin "4") (pinfunction "PC15-OSC32_OUT_4") (pintype "bidirectional"))
    )
  )
)
